# ShrewSpecsHat-1-2.net
KiCad netlist of a schematic drawn in EAGLE
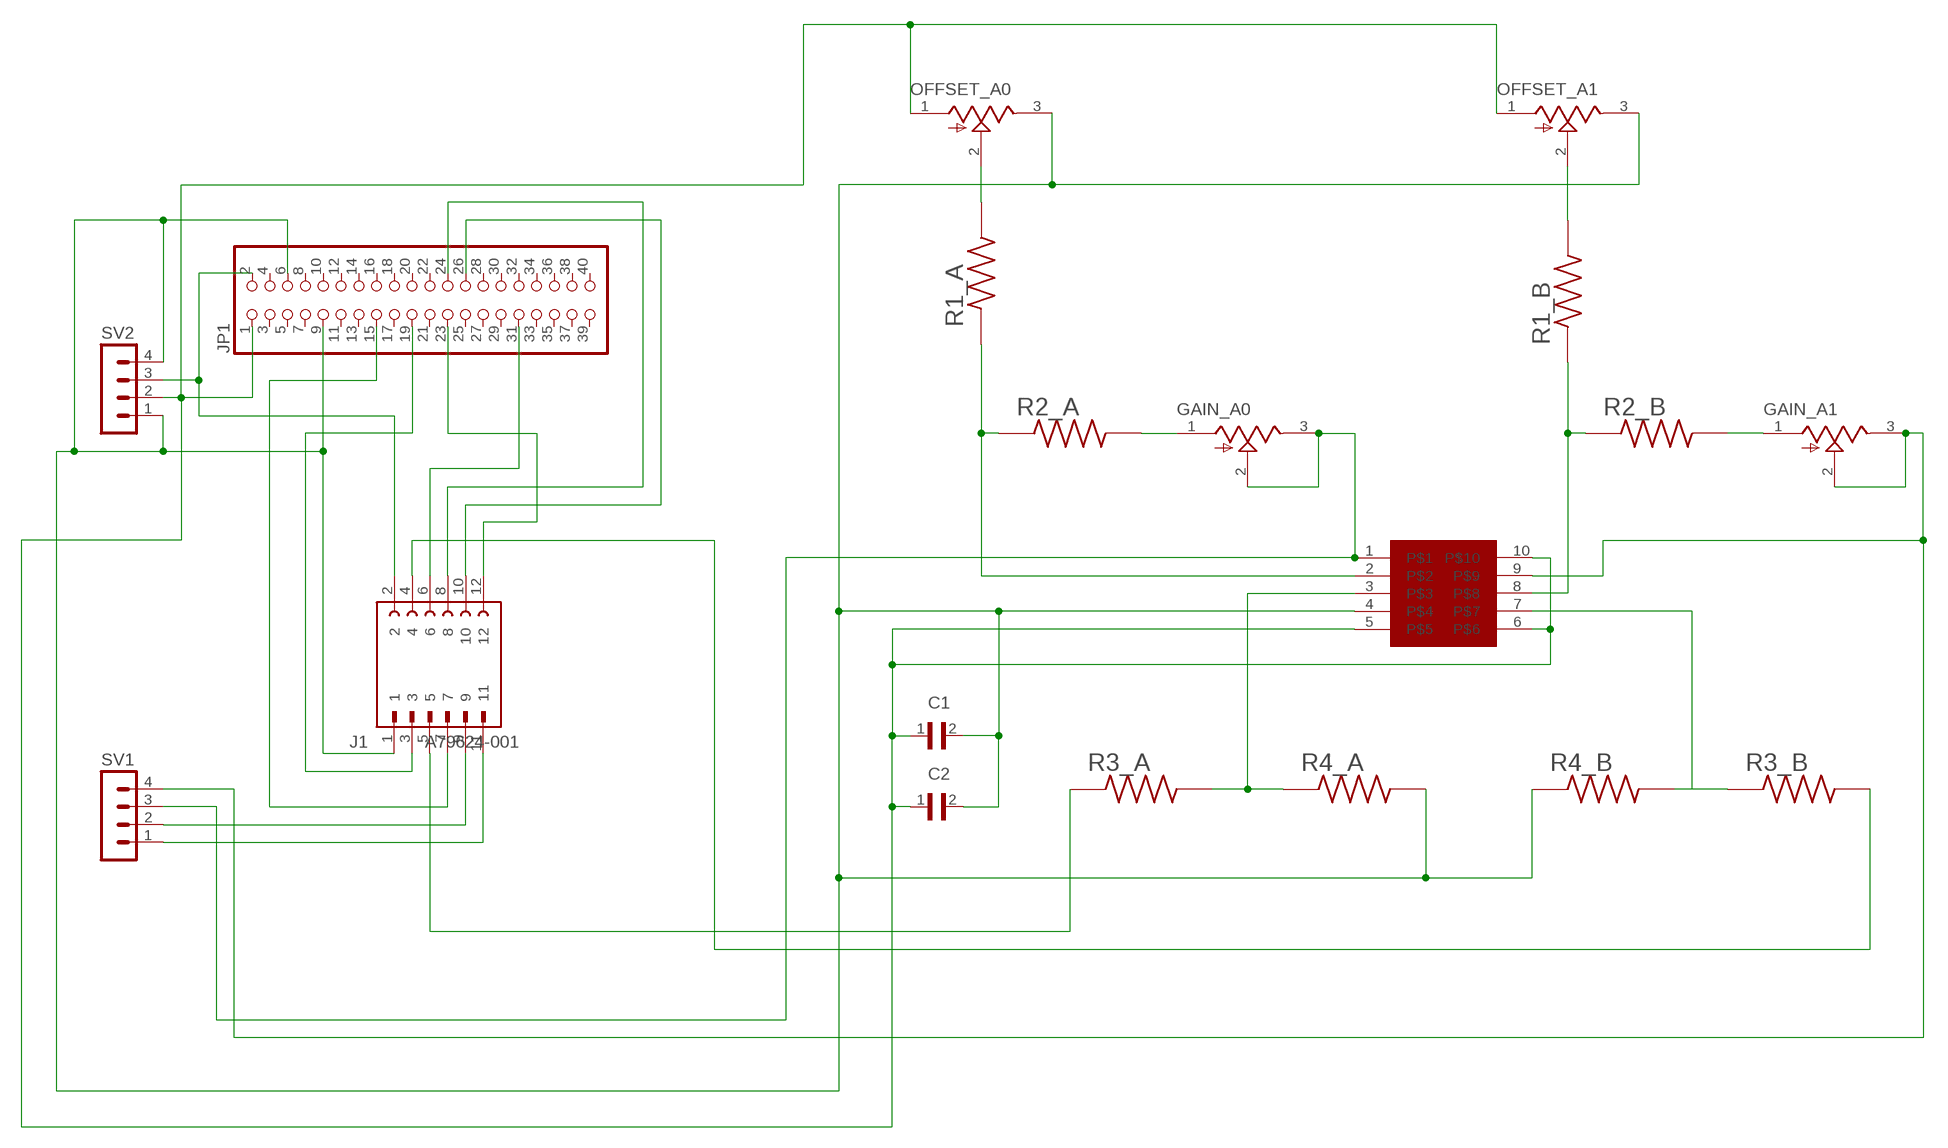
[diagram p0: schematic, sheet 1]

(export (version "E")
  (design (tool "Eeschema 10.0.6"))
  (components
    (comp (ref "C1")
      (value "CL21A106KOQNNNE")
      (footprint "eagle-import:CAPC2012X140N")
      (fields (field (name "MANUFACTURER") "Samsung Electro-Mechanics"))
      (libsource (lib "eagle-import") (part "CL21A106KOQNNNE"))
    )
    (comp (ref "C2")
      (value "CL21A106KOQNNNE")
      (footprint "eagle-import:CAPC2012X140N")
      (fields (field (name "MANUFACTURER") "Samsung Electro-Mechanics"))
      (libsource (lib "eagle-import") (part "CL21A106KOQNNNE"))
    )
    (comp (ref "GAIN_A0")
      (value "3362P-1-203LF")
      (footprint "eagle-import:TRIM_3362P-1-203LF")
      (fields (field (name "MF") "Bourns") (field (name "MP") "3362P-1-205LF"))
      (libsource (lib "eagle-import") (part "3362P-1-203LF"))
    )
    (comp (ref "GAIN_A1")
      (value "3362P-1-203LF")
      (footprint "eagle-import:TRIM_3362P-1-203LF")
      (fields (field (name "MF") "Bourns") (field (name "MP") "3362P-1-205LF"))
      (libsource (lib "eagle-import") (part "3362P-1-203LF"))
    )
    (comp (ref "J1")
      (value "A79624-001")
      (footprint "eagle-import:OMNETICS_A79624-001")
      (fields (field (name "MANUFACTURER") "Omnetics") (field (name "CREATOR") "DIZAR"))
      (libsource (lib "eagle-import") (part "A79624-001"))
    )
    (comp (ref "JP1")
      (value "PINHD-2X20-BIG")
      (footprint "eagle-import:2X20-BIG")
      (libsource (lib "eagle-import") (part "PINHD-2X20-BIG"))
    )
    (comp (ref "OFFSET_A0")
      (value "3362P-1-203LF")
      (footprint "eagle-import:TRIM_3362P-1-203LF")
      (fields (field (name "MF") "Bourns") (field (name "MP") "3362P-1-205LF"))
      (libsource (lib "eagle-import") (part "3362P-1-203LF"))
    )
    (comp (ref "OFFSET_A1")
      (value "3362P-1-203LF")
      (footprint "eagle-import:TRIM_3362P-1-203LF")
      (fields (field (name "MF") "Bourns") (field (name "MP") "3362P-1-205LF"))
      (libsource (lib "eagle-import") (part "3362P-1-203LF"))
    )
    (comp (ref "R1_A")
      (value "RC0805FR-07100RL")
      (footprint "eagle-import:RESC2012X60N")
      (libsource (lib "eagle-import") (part "RC0805FR-07100RL"))
    )
    (comp (ref "R1_B")
      (value "RC0805FR-07100RL")
      (footprint "eagle-import:RESC2012X60N")
      (libsource (lib "eagle-import") (part "RC0805FR-07100RL"))
    )
    (comp (ref "R2_A")
      (value "RC0805FR-07100RL")
      (footprint "eagle-import:RESC2012X60N")
      (libsource (lib "eagle-import") (part "RC0805FR-07100RL"))
    )
    (comp (ref "R2_B")
      (value "RC0805FR-07100RL")
      (footprint "eagle-import:RESC2012X60N")
      (libsource (lib "eagle-import") (part "RC0805FR-07100RL"))
    )
    (comp (ref "R3_A")
      (value "RC0805FR-07100RL")
      (footprint "eagle-import:RESC2012X60N")
      (libsource (lib "eagle-import") (part "RC0805FR-07100RL"))
    )
    (comp (ref "R3_B")
      (value "RC0805FR-07100RL")
      (footprint "eagle-import:RESC2012X60N")
      (libsource (lib "eagle-import") (part "RC0805FR-07100RL"))
    )
    (comp (ref "R4_A")
      (value "RC0805FR-07100RL")
      (footprint "eagle-import:RESC2012X60N")
      (libsource (lib "eagle-import") (part "RC0805FR-07100RL"))
    )
    (comp (ref "R4_B")
      (value "RC0805FR-07100RL")
      (footprint "eagle-import:RESC2012X60N")
      (libsource (lib "eagle-import") (part "RC0805FR-07100RL"))
    )
    (comp (ref "SV1")
      (value "MA04-1")
      (footprint "eagle-import:MA04-1")
      (libsource (lib "eagle-import") (part "MA04-1"))
    )
    (comp (ref "SV2")
      (value "MA04-1")
      (footprint "eagle-import:MA04-1")
      (libsource (lib "eagle-import") (part "MA04-1"))
    )
    (comp (ref "U$1")
      (value "SOP50P490X110-10N")
      (footprint "eagle-import:SOP50P490X110-10N")
      (libsource (lib "eagle-import") (part "SOP50P490X110-10N"))
    )
  )
  (nets
    (net (code "1") (name "Net-(GAIN_A0-CCW)") (class "Default")
      (node (ref "GAIN_A0") (pin "1") (pinfunction "CCW_1") (pintype "passive"))
      (node (ref "R2_A") (pin "2") (pinfunction "2_2") (pintype "passive"))
    )
    (net (code "2") (name "Net-(GAIN_A0-CW)") (class "Default")
      (node (ref "GAIN_A0") (pin "2") (pinfunction "WIPER_2") (pintype "passive"))
      (node (ref "GAIN_A0") (pin "3") (pinfunction "CW_3") (pintype "passive"))
      (node (ref "SV1") (pin "3") (pinfunction "3_3") (pintype "passive"))
      (node (ref "U$1") (pin "1") (pinfunction "P$1_1") (pintype "bidirectional"))
    )
    (net (code "3") (name "Net-(GAIN_A1-CCW)") (class "Default")
      (node (ref "GAIN_A1") (pin "1") (pinfunction "CCW_1") (pintype "passive"))
      (node (ref "R2_B") (pin "2") (pinfunction "2_2") (pintype "passive"))
    )
    (net (code "4") (name "Net-(GAIN_A1-CW)") (class "Default")
      (node (ref "GAIN_A1") (pin "2") (pinfunction "WIPER_2") (pintype "passive"))
      (node (ref "GAIN_A1") (pin "3") (pinfunction "CW_3") (pintype "passive"))
      (node (ref "SV1") (pin "4") (pinfunction "4_4") (pintype "passive"))
      (node (ref "U$1") (pin "9") (pinfunction "P$9_9") (pintype "bidirectional"))
    )
    (net (code "5") (name "Net-(J1-Pad2)") (class "Default")
      (node (ref "J1") (pin "2") (pinfunction "2_2") (pintype "passive"))
      (node (ref "JP1") (pin "2") (pinfunction "2_2") (pintype "passive"))
      (node (ref "SV2") (pin "3") (pinfunction "3_3") (pintype "passive"))
    )
    (net (code "6") (name "Net-(J1-Pad3)") (class "Default")
      (node (ref "J1") (pin "3") (pinfunction "3_3") (pintype "passive"))
      (node (ref "JP1") (pin "19") (pinfunction "19_19") (pintype "passive"))
    )
    (net (code "7") (name "Net-(J1-Pad4)") (class "Default")
      (node (ref "J1") (pin "4") (pinfunction "4_4") (pintype "passive"))
      (node (ref "R3_B") (pin "2") (pinfunction "2_2") (pintype "passive"))
    )
    (net (code "8") (name "Net-(J1-Pad5)") (class "Default")
      (node (ref "J1") (pin "5") (pinfunction "5_5") (pintype "passive"))
      (node (ref "R3_A") (pin "1") (pinfunction "1_1") (pintype "passive"))
    )
    (net (code "9") (name "Net-(J1-Pad6)") (class "Default")
      (node (ref "J1") (pin "6") (pinfunction "6_6") (pintype "passive"))
      (node (ref "JP1") (pin "31") (pinfunction "31_31") (pintype "passive"))
    )
    (net (code "10") (name "Net-(J1-Pad7)") (class "Default")
      (node (ref "J1") (pin "7") (pinfunction "7_7") (pintype "passive"))
      (node (ref "JP1") (pin "15") (pinfunction "15_15") (pintype "passive"))
    )
    (net (code "11") (name "Net-(J1-Pad8)") (class "Default")
      (node (ref "J1") (pin "8") (pinfunction "8_8") (pintype "passive"))
      (node (ref "JP1") (pin "24") (pinfunction "24_24") (pintype "passive"))
    )
    (net (code "12") (name "Net-(J1-Pad9)") (class "Default")
      (node (ref "J1") (pin "9") (pinfunction "9_9") (pintype "passive"))
      (node (ref "SV1") (pin "2") (pinfunction "2_2") (pintype "passive"))
    )
    (net (code "13") (name "Net-(J1-Pad10)") (class "Default")
      (node (ref "J1") (pin "10") (pinfunction "10_10") (pintype "passive"))
      (node (ref "JP1") (pin "26") (pinfunction "26_26") (pintype "passive"))
    )
    (net (code "14") (name "Net-(J1-Pad11)") (class "Default")
      (node (ref "J1") (pin "11") (pinfunction "11_11") (pintype "passive"))
      (node (ref "SV1") (pin "1") (pinfunction "1_1") (pintype "passive"))
    )
    (net (code "15") (name "Net-(J1-Pad12)") (class "Default")
      (node (ref "J1") (pin "12") (pinfunction "12_12") (pintype "passive"))
      (node (ref "JP1") (pin "23") (pinfunction "23_23") (pintype "passive"))
    )
    (net (code "16") (name "Net-(OFFSET_A0-CCW)") (class "Default")
      (node (ref "C1") (pin "1") (pinfunction "1_1") (pintype "passive"))
      (node (ref "C2") (pin "1") (pinfunction "1_1") (pintype "passive"))
      (node (ref "JP1") (pin "1") (pinfunction "1_1") (pintype "passive"))
      (node (ref "OFFSET_A0") (pin "1") (pinfunction "CCW_1") (pintype "passive"))
      (node (ref "OFFSET_A1") (pin "1") (pinfunction "CCW_1") (pintype "passive"))
      (node (ref "SV2") (pin "2") (pinfunction "2_2") (pintype "passive"))
      (node (ref "U$1") (pin "10") (pinfunction "P$10_10") (pintype "bidirectional"))
      (node (ref "U$1") (pin "5") (pinfunction "P$5_5") (pintype "bidirectional"))
      (node (ref "U$1") (pin "6") (pinfunction "P$6_6") (pintype "bidirectional"))
    )
    (net (code "17") (name "Net-(OFFSET_A0-CW)") (class "Default")
      (node (ref "C1") (pin "2") (pinfunction "2_2") (pintype "passive"))
      (node (ref "C2") (pin "2") (pinfunction "2_2") (pintype "passive"))
      (node (ref "J1") (pin "1") (pinfunction "1_1") (pintype "passive"))
      (node (ref "JP1") (pin "6") (pinfunction "6_6") (pintype "passive"))
      (node (ref "JP1") (pin "9") (pinfunction "9_9") (pintype "passive"))
      (node (ref "OFFSET_A0") (pin "3") (pinfunction "CW_3") (pintype "passive"))
      (node (ref "OFFSET_A1") (pin "3") (pinfunction "CW_3") (pintype "passive"))
      (node (ref "R4_A") (pin "2") (pinfunction "2_2") (pintype "passive"))
      (node (ref "R4_B") (pin "1") (pinfunction "1_1") (pintype "passive"))
      (node (ref "SV2") (pin "1") (pinfunction "1_1") (pintype "passive"))
      (node (ref "SV2") (pin "4") (pinfunction "4_4") (pintype "passive"))
      (node (ref "U$1") (pin "4") (pinfunction "P$4_4") (pintype "bidirectional"))
    )
    (net (code "18") (name "Net-(OFFSET_A0-WIPER)") (class "Default")
      (node (ref "OFFSET_A0") (pin "2") (pinfunction "WIPER_2") (pintype "passive"))
      (node (ref "R1_A") (pin "2") (pinfunction "2_2") (pintype "passive"))
    )
    (net (code "19") (name "Net-(OFFSET_A1-WIPER)") (class "Default")
      (node (ref "OFFSET_A1") (pin "2") (pinfunction "WIPER_2") (pintype "passive"))
      (node (ref "R1_B") (pin "2") (pinfunction "2_2") (pintype "passive"))
    )
    (net (code "20") (name "Net-(U$1-P$2)") (class "Default")
      (node (ref "R1_A") (pin "1") (pinfunction "1_1") (pintype "passive"))
      (node (ref "R2_A") (pin "1") (pinfunction "1_1") (pintype "passive"))
      (node (ref "U$1") (pin "2") (pinfunction "P$2_2") (pintype "bidirectional"))
    )
    (net (code "21") (name "Net-(U$1-P$3)") (class "Default")
      (node (ref "R3_A") (pin "2") (pinfunction "2_2") (pintype "passive"))
      (node (ref "R4_A") (pin "1") (pinfunction "1_1") (pintype "passive"))
      (node (ref "U$1") (pin "3") (pinfunction "P$3_3") (pintype "bidirectional"))
    )
    (net (code "22") (name "Net-(U$1-P$7)") (class "Default")
      (node (ref "R3_B") (pin "1") (pinfunction "1_1") (pintype "passive"))
      (node (ref "R4_B") (pin "2") (pinfunction "2_2") (pintype "passive"))
      (node (ref "U$1") (pin "7") (pinfunction "P$7_7") (pintype "bidirectional"))
    )
    (net (code "23") (name "Net-(U$1-P$8)") (class "Default")
      (node (ref "R1_B") (pin "1") (pinfunction "1_1") (pintype "passive"))
      (node (ref "R2_B") (pin "1") (pinfunction "1_1") (pintype "passive"))
      (node (ref "U$1") (pin "8") (pinfunction "P$8_8") (pintype "bidirectional"))
    )
    (net (code "24") (name "unconnected-(JP1-Pad3)") (class "Default")
      (node (ref "JP1") (pin "3") (pinfunction "3_3") (pintype "passive"))
    )
    (net (code "25") (name "unconnected-(JP1-Pad4)") (class "Default")
      (node (ref "JP1") (pin "4") (pinfunction "4_4") (pintype "passive"))
    )
    (net (code "26") (name "unconnected-(JP1-Pad5)") (class "Default")
      (node (ref "JP1") (pin "5") (pinfunction "5_5") (pintype "passive"))
    )
    (net (code "27") (name "unconnected-(JP1-Pad7)") (class "Default")
      (node (ref "JP1") (pin "7") (pinfunction "7_7") (pintype "passive"))
    )
    (net (code "28") (name "unconnected-(JP1-Pad8)") (class "Default")
      (node (ref "JP1") (pin "8") (pinfunction "8_8") (pintype "passive"))
    )
    (net (code "29") (name "unconnected-(JP1-Pad10)") (class "Default")
      (node (ref "JP1") (pin "10") (pinfunction "10_10") (pintype "passive"))
    )
    (net (code "30") (name "unconnected-(JP1-Pad11)") (class "Default")
      (node (ref "JP1") (pin "11") (pinfunction "11_11") (pintype "passive"))
    )
    (net (code "31") (name "unconnected-(JP1-Pad12)") (class "Default")
      (node (ref "JP1") (pin "12") (pinfunction "12_12") (pintype "passive"))
    )
    (net (code "32") (name "unconnected-(JP1-Pad13)") (class "Default")
      (node (ref "JP1") (pin "13") (pinfunction "13_13") (pintype "passive"))
    )
    (net (code "33") (name "unconnected-(JP1-Pad14)") (class "Default")
      (node (ref "JP1") (pin "14") (pinfunction "14_14") (pintype "passive"))
    )
    (net (code "34") (name "unconnected-(JP1-Pad16)") (class "Default")
      (node (ref "JP1") (pin "16") (pinfunction "16_16") (pintype "passive"))
    )
    (net (code "35") (name "unconnected-(JP1-Pad17)") (class "Default")
      (node (ref "JP1") (pin "17") (pinfunction "17_17") (pintype "passive"))
    )
    (net (code "36") (name "unconnected-(JP1-Pad18)") (class "Default")
      (node (ref "JP1") (pin "18") (pinfunction "18_18") (pintype "passive"))
    )
    (net (code "37") (name "unconnected-(JP1-Pad20)") (class "Default")
      (node (ref "JP1") (pin "20") (pinfunction "20_20") (pintype "passive"))
    )
    (net (code "38") (name "unconnected-(JP1-Pad21)") (class "Default")
      (node (ref "JP1") (pin "21") (pinfunction "21_21") (pintype "passive"))
    )
    (net (code "39") (name "unconnected-(JP1-Pad22)") (class "Default")
      (node (ref "JP1") (pin "22") (pinfunction "22_22") (pintype "passive"))
    )
    (net (code "40") (name "unconnected-(JP1-Pad25)") (class "Default")
      (node (ref "JP1") (pin "25") (pinfunction "25_25") (pintype "passive"))
    )
    (net (code "41") (name "unconnected-(JP1-Pad27)") (class "Default")
      (node (ref "JP1") (pin "27") (pinfunction "27_27") (pintype "passive"))
    )
    (net (code "42") (name "unconnected-(JP1-Pad28)") (class "Default")
      (node (ref "JP1") (pin "28") (pinfunction "28_28") (pintype "passive"))
    )
    (net (code "43") (name "unconnected-(JP1-Pad29)") (class "Default")
      (node (ref "JP1") (pin "29") (pinfunction "29_29") (pintype "passive"))
    )
    (net (code "44") (name "unconnected-(JP1-Pad30)") (class "Default")
      (node (ref "JP1") (pin "30") (pinfunction "30_30") (pintype "passive"))
    )
    (net (code "45") (name "unconnected-(JP1-Pad32)") (class "Default")
      (node (ref "JP1") (pin "32") (pinfunction "32_32") (pintype "passive"))
    )
    (net (code "46") (name "unconnected-(JP1-Pad33)") (class "Default")
      (node (ref "JP1") (pin "33") (pinfunction "33_33") (pintype "passive"))
    )
    (net (code "47") (name "unconnected-(JP1-Pad34)") (class "Default")
      (node (ref "JP1") (pin "34") (pinfunction "34_34") (pintype "passive"))
    )
    (net (code "48") (name "unconnected-(JP1-Pad35)") (class "Default")
      (node (ref "JP1") (pin "35") (pinfunction "35_35") (pintype "passive"))
    )
    (net (code "49") (name "unconnected-(JP1-Pad36)") (class "Default")
      (node (ref "JP1") (pin "36") (pinfunction "36_36") (pintype "passive"))
    )
    (net (code "50") (name "unconnected-(JP1-Pad37)") (class "Default")
      (node (ref "JP1") (pin "37") (pinfunction "37_37") (pintype "passive"))
    )
    (net (code "51") (name "unconnected-(JP1-Pad38)") (class "Default")
      (node (ref "JP1") (pin "38") (pinfunction "38_38") (pintype "passive"))
    )
    (net (code "52") (name "unconnected-(JP1-Pad39)") (class "Default")
      (node (ref "JP1") (pin "39") (pinfunction "39_39") (pintype "passive"))
    )
    (net (code "53") (name "unconnected-(JP1-Pad40)") (class "Default")
      (node (ref "JP1") (pin "40") (pinfunction "40_40") (pintype "passive"))
    )
  )
)
